# SparkSwitch_Small.net
KiCad netlist of a schematic drawn in EAGLE
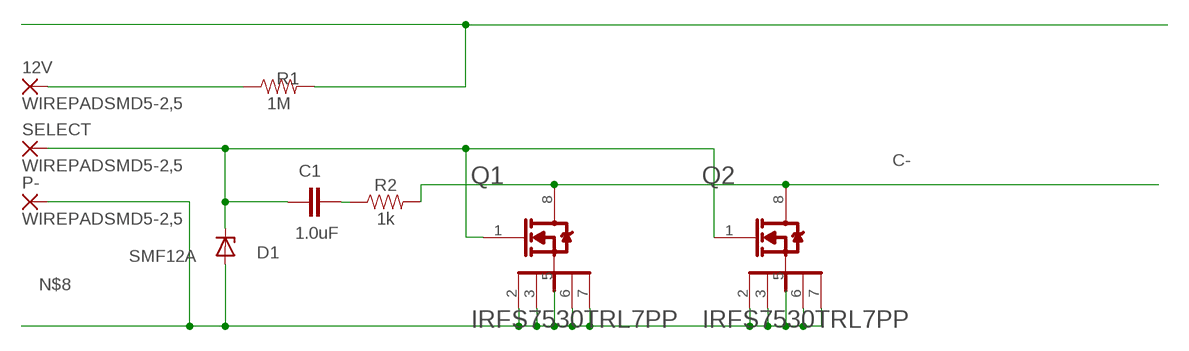
[diagram p0: schematic, sheet 1]

(export (version "E")
  (design (tool "Eeschema 10.0.6"))
  (components
    (comp (ref "12V")
      (value "WIREPADSMD5-2,5")
      (footprint "eagle-import:5-2,5")
      (libsource (lib "eagle-import") (part "WIREPADSMD5-2,5"))
    )
    (comp (ref "C1")
      (value "1.0uF")
      (footprint "eagle-import:0805")
      (libsource (lib "eagle-import") (part "1.0UF-0805-25V-(+80/-20%)"))
    )
    (comp (ref "D1")
      (value "SMF12A")
      (footprint "eagle-import:SOD123F")
      (fields (field (name "MF") "Littelfuse"))
      (libsource (lib "eagle-import") (part "SMFA12"))
    )
    (comp (ref "P-")
      (value "WIREPADSMD5-2,5")
      (footprint "eagle-import:5-2,5")
      (libsource (lib "eagle-import") (part "WIREPADSMD5-2,5"))
    )
    (comp (ref "Q1")
      (value "INFINEON_IRFS7530TRL7PPINFINEON_IRFS7530TRL7PP_0_0")
      (footprint "eagle-import:INFINEON_IRFS7530TRL7PP_0")
      (fields
        (field (name "DIGIKEY_PART_NUMBER") "IRFS7530TRL7PPCT-ND")
        (field (name "MF") "Infineon")
        (field (name "MOUSER_PART_NUMBER") "942-IRFS7530TRL7PP")
      )
      (libsource (lib "eagle-import") (part "INFINEON_IRFS7530TRL7PPINFINEON_IRFS7530TRL7PP_0_0"))
    )
    (comp (ref "Q2")
      (value "INFINEON_IRFS7530TRL7PPINFINEON_IRFS7530TRL7PP_0_0")
      (footprint "eagle-import:INFINEON_IRFS7530TRL7PP_0")
      (fields
        (field (name "DIGIKEY_PART_NUMBER") "IRFS7530TRL7PPCT-ND")
        (field (name "MF") "Infineon")
        (field (name "MOUSER_PART_NUMBER") "942-IRFS7530TRL7PP")
      )
      (libsource (lib "eagle-import") (part "INFINEON_IRFS7530TRL7PPINFINEON_IRFS7530TRL7PP_0_0"))
    )
    (comp (ref "R1")
      (value "1M")
      (footprint "eagle-import:0603")
      (libsource (lib "eagle-import") (part "1MOHM-0603-1/4W-5%"))
    )
    (comp (ref "R2")
      (value "1k")
      (footprint "eagle-import:0603")
      (libsource (lib "eagle-import") (part "1KOHM-0603-1/10W-1%"))
    )
    (comp (ref "SELECT")
      (value "WIREPADSMD5-2,5")
      (footprint "eagle-import:5-2,5")
      (libsource (lib "eagle-import") (part "WIREPADSMD5-2,5"))
    )
  )
  (nets
    (net (code "1") (name "/C-") (class "Default")
      (node (ref "Q1") (pin "8") (pinfunction "D_8") (pintype "passive"))
      (node (ref "Q2") (pin "8") (pinfunction "D_8") (pintype "passive"))
      (node (ref "R2") (pin "2") (pinfunction "2_2") (pintype "passive"))
    )
    (net (code "2") (name "/N$8") (class "Default")
      (node (ref "D1") (pin "A") (pinfunction "A_A") (pintype "passive"))
      (node (ref "P-") (pin "1") (pinfunction "P_1") (pintype "passive"))
      (node (ref "Q1") (pin "2") (pinfunction "1_S_2") (pintype "passive"))
      (node (ref "Q1") (pin "3") (pinfunction "2_S_3") (pintype "passive"))
      (node (ref "Q1") (pin "5") (pinfunction "3_S_5") (pintype "passive"))
      (node (ref "Q1") (pin "6") (pinfunction "4_S_6") (pintype "passive"))
      (node (ref "Q1") (pin "7") (pinfunction "5_S_7") (pintype "passive"))
      (node (ref "Q2") (pin "2") (pinfunction "1_S_2") (pintype "passive"))
      (node (ref "Q2") (pin "3") (pinfunction "2_S_3") (pintype "passive"))
      (node (ref "Q2") (pin "5") (pinfunction "3_S_5") (pintype "passive"))
      (node (ref "Q2") (pin "6") (pinfunction "4_S_6") (pintype "passive"))
      (node (ref "Q2") (pin "7") (pinfunction "5_S_7") (pintype "passive"))
    )
    (net (code "3") (name "Net-(12V-P)") (class "Default")
      (node (ref "12V") (pin "1") (pinfunction "P_1") (pintype "passive"))
      (node (ref "R1") (pin "1") (pinfunction "1_1") (pintype "passive"))
    )
    (net (code "4") (name "Net-(C1-Pad2)") (class "Default")
      (node (ref "C1") (pin "2") (pinfunction "2_2") (pintype "passive"))
      (node (ref "R2") (pin "1") (pinfunction "1_1") (pintype "passive"))
    )
    (net (code "5") (name "Net-(Q1-G)") (class "Default")
      (node (ref "C1") (pin "1") (pinfunction "1_1") (pintype "passive"))
      (node (ref "D1") (pin "C") (pinfunction "C_C") (pintype "passive"))
      (node (ref "Q1") (pin "1") (pinfunction "G_1") (pintype "passive"))
      (node (ref "Q2") (pin "1") (pinfunction "G_1") (pintype "passive"))
      (node (ref "SELECT") (pin "1") (pinfunction "P_1") (pintype "passive"))
    )
    (net (code "6") (name "unconnected-(R1-Pad2)") (class "Default")
      (node (ref "R1") (pin "2") (pinfunction "2_2") (pintype "passive"))
    )
  )
)
